# motiondetector.net
KiCad netlist of a schematic drawn in EAGLE
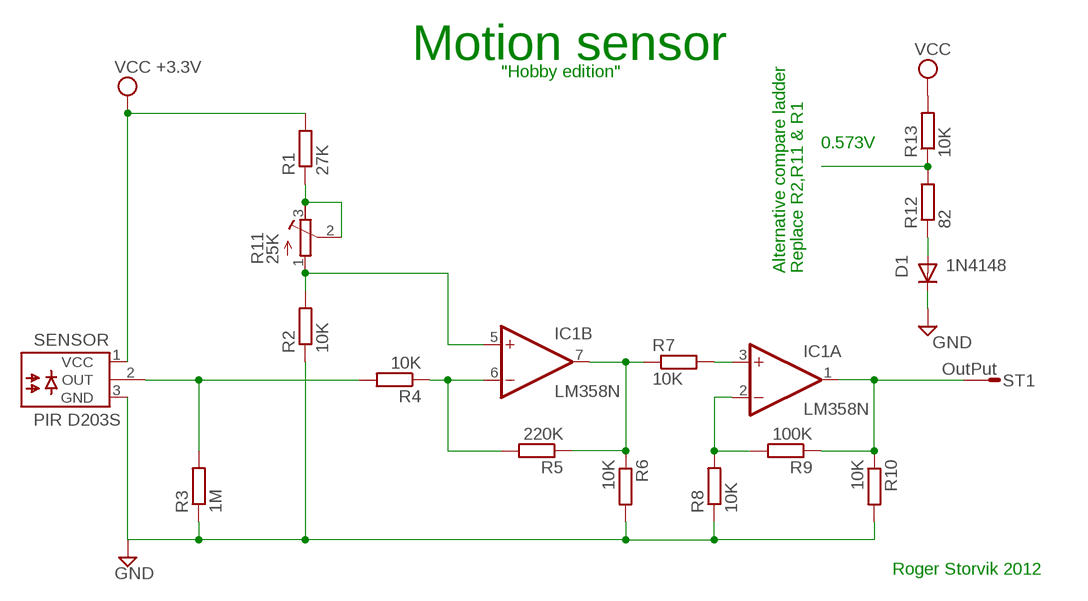
[diagram p0: schematic, sheet 1]

(export (version "E")
  (design (tool "Eeschema 10.0.6"))
  (components
    (comp (ref "D1")
      (value "1N4148")
      (footprint "eagle-import:DO35-7")
      (libsource (lib "eagle-import") (part "1N4148DO35-7"))
    )
    (comp (ref "IC1")
      (value "LM358N")
      (footprint "eagle-import:DIL08")
      (libsource (lib "eagle-import") (part "LM358N"))
    )
    (comp (ref "R1")
      (value "27K")
      (footprint "eagle-import:0204_5")
      (libsource (lib "eagle-import") (part "R-EU_0204/5"))
    )
    (comp (ref "R2")
      (value "10K")
      (footprint "eagle-import:0204_5")
      (libsource (lib "eagle-import") (part "R-EU_0204/5"))
    )
    (comp (ref "R3")
      (value "1M")
      (footprint "eagle-import:0204_5")
      (libsource (lib "eagle-import") (part "R-EU_0204/5"))
    )
    (comp (ref "R4")
      (value "10K")
      (footprint "eagle-import:0204_5")
      (libsource (lib "eagle-import") (part "R-EU_0204/5"))
    )
    (comp (ref "R5")
      (value "220K")
      (footprint "eagle-import:0204_5")
      (libsource (lib "eagle-import") (part "R-EU_0204/5"))
    )
    (comp (ref "R6")
      (value "10K")
      (footprint "eagle-import:0204_5")
      (libsource (lib "eagle-import") (part "R-EU_0204/5"))
    )
    (comp (ref "R7")
      (value "10K")
      (footprint "eagle-import:0204_5")
      (libsource (lib "eagle-import") (part "R-EU_0204/5"))
    )
    (comp (ref "R8")
      (value "10K")
      (footprint "eagle-import:0204_5")
      (libsource (lib "eagle-import") (part "R-EU_0204/5"))
    )
    (comp (ref "R9")
      (value "100K")
      (footprint "eagle-import:0204_5")
      (libsource (lib "eagle-import") (part "R-EU_0204/5"))
    )
    (comp (ref "R10")
      (value "10K")
      (footprint "eagle-import:0204_5")
      (libsource (lib "eagle-import") (part "R-EU_0204/5"))
    )
    (comp (ref "R11")
      (value "25K")
      (footprint "eagle-import:RTRIM64W")
      (libsource (lib "eagle-import") (part "R-TRIMM64W"))
    )
    (comp (ref "R12")
      (value "82")
      (footprint "eagle-import:0204_5")
      (libsource (lib "eagle-import") (part "R-EU_0204/5"))
    )
    (comp (ref "R13")
      (value "10K")
      (footprint "eagle-import:0204_5")
      (libsource (lib "eagle-import") (part "R-EU_0204/5"))
    )
    (comp (ref "SENSOR")
      (value "PIR D203S")
      (footprint "eagle-import:TO18PL3")
      (libsource (lib "eagle-import") (part "HFD3031"))
    )
    (comp (ref "ST1")
      (value "OutPut")
      (footprint "eagle-import:ST2,8")
      (libsource (lib "eagle-import") (part "ST2,8"))
    )
  )
  (nets
    (net (code "1") (name "GND") (class "Default")
      (node (ref "D1") (pin "C") (pinfunction "C_C") (pintype "passive"))
      (node (ref "R10") (pin "2") (pinfunction "2_2") (pintype "passive"))
      (node (ref "R2") (pin "1") (pinfunction "1_1") (pintype "passive"))
      (node (ref "R3") (pin "1") (pinfunction "1_1") (pintype "passive"))
      (node (ref "R6") (pin "2") (pinfunction "2_2") (pintype "passive"))
      (node (ref "R8") (pin "1") (pinfunction "1_1") (pintype "passive"))
      (node (ref "SENSOR") (pin "3") (pinfunction "GND_3") (pintype "power_in"))
    )
    (net (code "2") (name "Net-(D1-PadA)") (class "Default")
      (node (ref "D1") (pin "A") (pinfunction "A_A") (pintype "passive"))
      (node (ref "R12") (pin "1") (pinfunction "1_1") (pintype "passive"))
    )
    (net (code "3") (name "Net-(IC1A-+IN)") (class "Default")
      (node (ref "IC1") (pin "3") (pinfunction "+IN_3") (pintype "input"))
      (node (ref "R7") (pin "2") (pinfunction "2_2") (pintype "passive"))
    )
    (net (code "4") (name "Net-(IC1A--IN)") (class "Default")
      (node (ref "IC1") (pin "2") (pinfunction "-IN_2") (pintype "input"))
      (node (ref "R8") (pin "2") (pinfunction "2_2") (pintype "passive"))
      (node (ref "R9") (pin "2") (pinfunction "2_2") (pintype "passive"))
    )
    (net (code "5") (name "Net-(IC1A-OUT)") (class "Default")
      (node (ref "IC1") (pin "1") (pinfunction "OUT_1") (pintype "output"))
      (node (ref "R10") (pin "1") (pinfunction "1_1") (pintype "passive"))
      (node (ref "R9") (pin "1") (pinfunction "1_1") (pintype "passive"))
      (node (ref "ST1") (pin "1") (pinfunction "ST_1") (pintype "passive"))
    )
    (net (code "6") (name "Net-(IC1B-+IN)") (class "Default")
      (node (ref "IC1") (pin "5") (pinfunction "+IN_5") (pintype "input"))
      (node (ref "R11") (pin "1") (pinfunction "E_1") (pintype "passive"))
      (node (ref "R2") (pin "2") (pinfunction "2_2") (pintype "passive"))
    )
    (net (code "7") (name "Net-(IC1B--IN)") (class "Default")
      (node (ref "IC1") (pin "6") (pinfunction "-IN_6") (pintype "input"))
      (node (ref "R4") (pin "1") (pinfunction "1_1") (pintype "passive"))
      (node (ref "R5") (pin "2") (pinfunction "2_2") (pintype "passive"))
    )
    (net (code "8") (name "Net-(IC1B-OUT)") (class "Default")
      (node (ref "IC1") (pin "7") (pinfunction "OUT_7") (pintype "output"))
      (node (ref "R5") (pin "1") (pinfunction "1_1") (pintype "passive"))
      (node (ref "R6") (pin "1") (pinfunction "1_1") (pintype "passive"))
      (node (ref "R7") (pin "1") (pinfunction "1_1") (pintype "passive"))
    )
    (net (code "9") (name "Net-(R11-A)") (class "Default")
      (node (ref "R1") (pin "1") (pinfunction "1_1") (pintype "passive"))
      (node (ref "R11") (pin "2") (pinfunction "S_2") (pintype "passive"))
      (node (ref "R11") (pin "3") (pinfunction "A_3") (pintype "passive"))
    )
    (net (code "10") (name "Net-(R12-Pad2)") (class "Default")
      (node (ref "R12") (pin "2") (pinfunction "2_2") (pintype "passive"))
      (node (ref "R13") (pin "1") (pinfunction "1_1") (pintype "passive"))
    )
    (net (code "11") (name "Net-(SENSOR-OUT)") (class "Default")
      (node (ref "R3") (pin "2") (pinfunction "2_2") (pintype "passive"))
      (node (ref "R4") (pin "2") (pinfunction "2_2") (pintype "passive"))
      (node (ref "SENSOR") (pin "2") (pinfunction "OUT_2") (pintype "output"))
    )
    (net (code "12") (name "VCC") (class "Default")
      (node (ref "R1") (pin "2") (pinfunction "2_2") (pintype "passive"))
      (node (ref "R13") (pin "2") (pinfunction "2_2") (pintype "passive"))
      (node (ref "SENSOR") (pin "1") (pinfunction "VCC_1") (pintype "power_in"))
    )
  )
)
